# BLDC.net
KiCad netlist of a schematic drawn in EasyEDA Pro
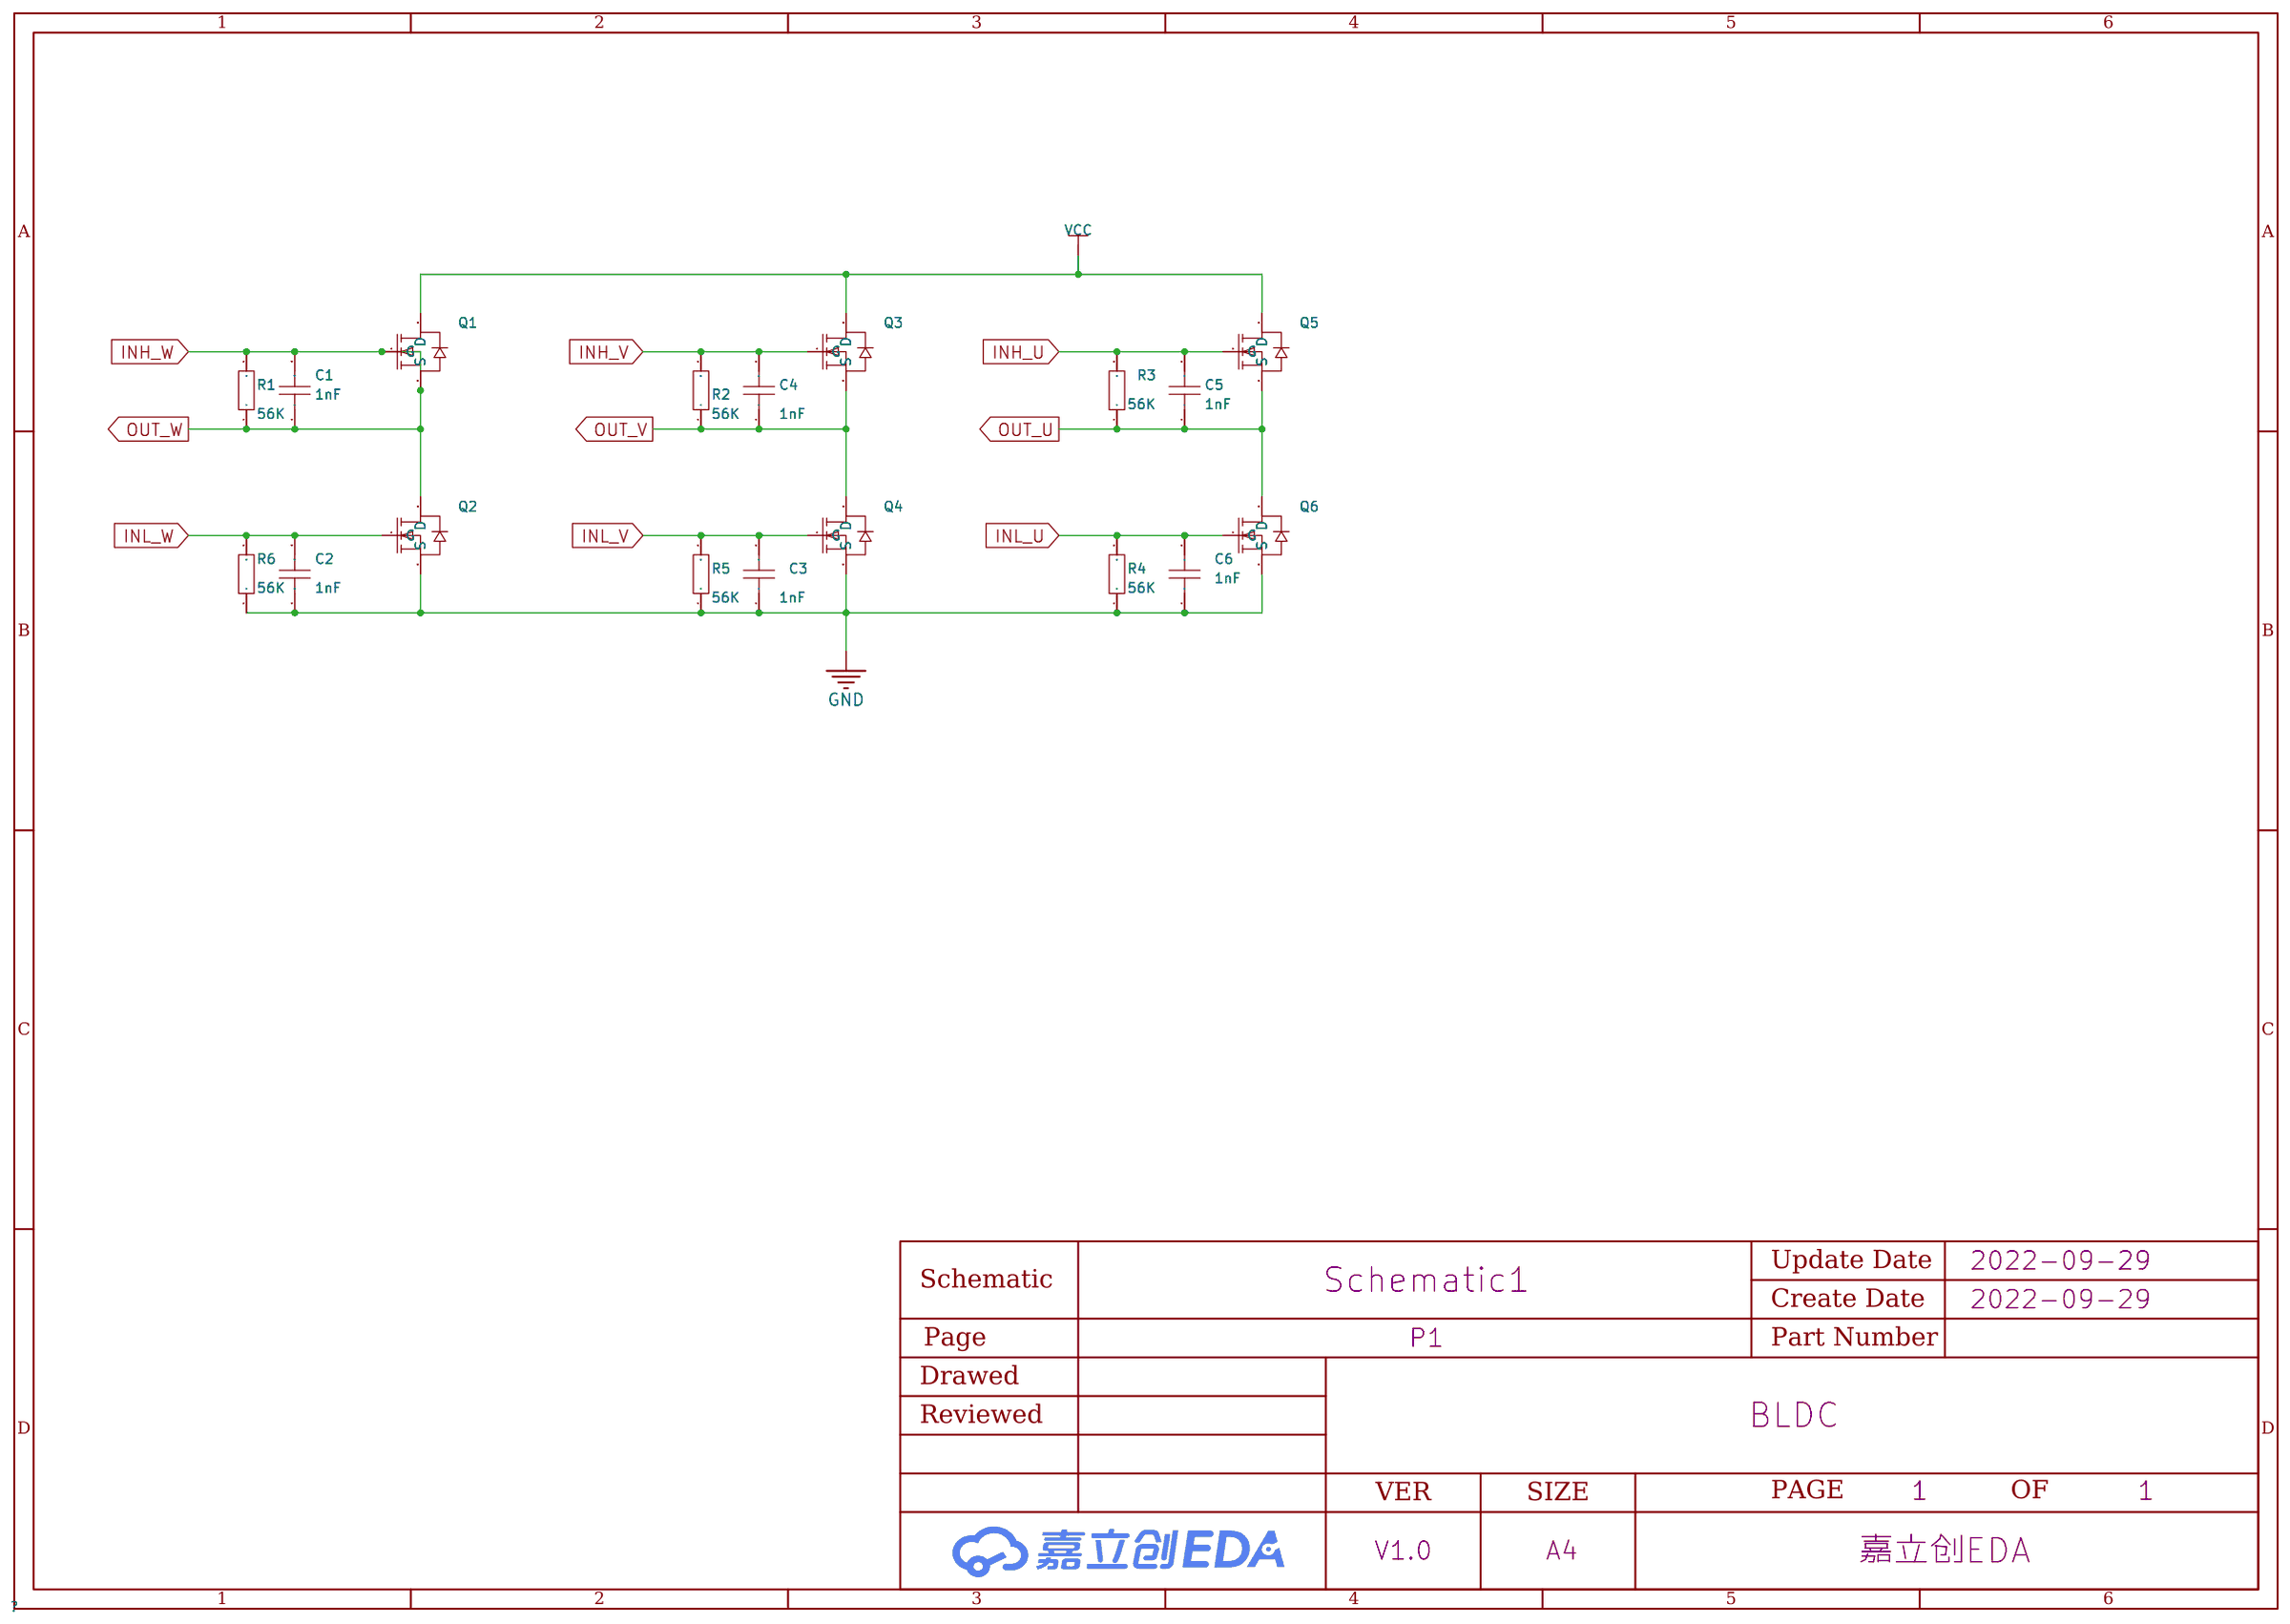
[diagram p0: schematic sheet]

(export (version "E")
  (design (tool "Eeschema 10.0.6"))
  (components
    (comp (ref "C1")
      (value "1nF")
      (footprint "easyedapro:C0603")
      (libsource (lib "easyedapro") (part "C1210X7R475K630NT"))
    )
    (comp (ref "C2")
      (value "1nF")
      (footprint "easyedapro:C0603")
      (libsource (lib "easyedapro") (part "C1210X7R475K630NT"))
    )
    (comp (ref "C3")
      (value "1nF")
      (footprint "easyedapro:C0603")
      (libsource (lib "easyedapro") (part "C1210X7R475K630NT"))
    )
    (comp (ref "C4")
      (value "1nF")
      (footprint "easyedapro:C0603")
      (libsource (lib "easyedapro") (part "C1210X7R475K630NT"))
    )
    (comp (ref "C5")
      (value "1nF")
      (footprint "easyedapro:C0603")
      (libsource (lib "easyedapro") (part "C1210X7R475K630NT"))
    )
    (comp (ref "C6")
      (value "1nF")
      (footprint "easyedapro:C0603")
      (libsource (lib "easyedapro") (part "C1210X7R475K630NT"))
    )
    (comp (ref "Q1")
      (value "~")
      (footprint "easyedapro:SOT-23-3_L2.9-W1.3-P1.90-LS2.4-BR")
      (libsource (lib "easyedapro") (part "N_MOS"))
    )
    (comp (ref "Q2")
      (value "~")
      (footprint "easyedapro:SOT-23-3_L2.9-W1.3-P1.90-LS2.4-BR")
      (libsource (lib "easyedapro") (part "N_MOS"))
    )
    (comp (ref "Q3")
      (value "~")
      (footprint "easyedapro:SOT-23-3_L2.9-W1.3-P1.90-LS2.4-BR")
      (libsource (lib "easyedapro") (part "N_MOS"))
    )
    (comp (ref "Q4")
      (value "~")
      (footprint "easyedapro:SOT-23-3_L2.9-W1.3-P1.90-LS2.4-BR")
      (libsource (lib "easyedapro") (part "N_MOS"))
    )
    (comp (ref "Q5")
      (value "~")
      (footprint "easyedapro:SOT-23-3_L2.9-W1.3-P1.90-LS2.4-BR")
      (libsource (lib "easyedapro") (part "N_MOS"))
    )
    (comp (ref "Q6")
      (value "~")
      (footprint "easyedapro:SOT-23-3_L2.9-W1.3-P1.90-LS2.4-BR")
      (libsource (lib "easyedapro") (part "N_MOS"))
    )
    (comp (ref "R1") (value "56K") (footprint "easyedapro:R0603") (libsource (lib "easyedapro") (part "电阻")))
    (comp (ref "R2") (value "56K") (footprint "easyedapro:R0603") (libsource (lib "easyedapro") (part "电阻")))
    (comp (ref "R3") (value "56K") (footprint "easyedapro:R0603") (libsource (lib "easyedapro") (part "电阻")))
    (comp (ref "R4") (value "56K") (footprint "easyedapro:R0603") (libsource (lib "easyedapro") (part "电阻")))
    (comp (ref "R5") (value "56K") (footprint "easyedapro:R0603") (libsource (lib "easyedapro") (part "电阻")))
    (comp (ref "R6") (value "56K") (footprint "easyedapro:R0603") (libsource (lib "easyedapro") (part "电阻")))
  )
  (nets
    (net (code "1") (name "GND") (class "Default")
      (node (ref "C2") (pin "1") (pinfunction "1_1") (pintype "input"))
      (node (ref "C3") (pin "1") (pinfunction "1_1") (pintype "input"))
      (node (ref "C6") (pin "1") (pinfunction "1_1") (pintype "input"))
      (node (ref "Q2") (pin "2") (pinfunction "S_2") (pintype "input"))
      (node (ref "Q4") (pin "2") (pinfunction "S_2") (pintype "input"))
      (node (ref "Q6") (pin "2") (pinfunction "S_2") (pintype "input"))
      (node (ref "R4") (pin "1") (pinfunction "1_1") (pintype "input"))
      (node (ref "R5") (pin "1") (pinfunction "1_1") (pintype "input"))
      (node (ref "R6") (pin "1") (pinfunction "1_1") (pintype "input"))
    )
    (net (code "2") (name "INH_U") (class "Default")
      (node (ref "C5") (pin "2") (pinfunction "2_2") (pintype "input"))
      (node (ref "Q5") (pin "1") (pinfunction "G_1") (pintype "input"))
      (node (ref "R3") (pin "2") (pinfunction "2_2") (pintype "input"))
    )
    (net (code "3") (name "INH_V") (class "Default")
      (node (ref "C4") (pin "2") (pinfunction "2_2") (pintype "input"))
      (node (ref "Q3") (pin "1") (pinfunction "G_1") (pintype "input"))
      (node (ref "R2") (pin "2") (pinfunction "2_2") (pintype "input"))
    )
    (net (code "4") (name "INH_W") (class "Default")
      (node (ref "C1") (pin "1") (pinfunction "1_1") (pintype "input"))
      (node (ref "C1") (pin "2") (pinfunction "2_2") (pintype "input"))
      (node (ref "Q1") (pin "1") (pinfunction "G_1") (pintype "input"))
      (node (ref "Q1") (pin "2") (pinfunction "S_2") (pintype "input"))
      (node (ref "Q2") (pin "3") (pinfunction "D_3") (pintype "input"))
      (node (ref "R1") (pin "1") (pinfunction "1_1") (pintype "input"))
      (node (ref "R1") (pin "2") (pinfunction "2_2") (pintype "input"))
    )
    (net (code "5") (name "INL_U") (class "Default")
      (node (ref "C6") (pin "2") (pinfunction "2_2") (pintype "input"))
      (node (ref "Q6") (pin "1") (pinfunction "G_1") (pintype "input"))
      (node (ref "R4") (pin "2") (pinfunction "2_2") (pintype "input"))
    )
    (net (code "6") (name "INL_V") (class "Default")
      (node (ref "C3") (pin "2") (pinfunction "2_2") (pintype "input"))
      (node (ref "Q4") (pin "1") (pinfunction "G_1") (pintype "input"))
      (node (ref "R5") (pin "2") (pinfunction "2_2") (pintype "input"))
    )
    (net (code "7") (name "INL_W") (class "Default")
      (node (ref "C2") (pin "2") (pinfunction "2_2") (pintype "input"))
      (node (ref "Q2") (pin "1") (pinfunction "G_1") (pintype "input"))
      (node (ref "R6") (pin "2") (pinfunction "2_2") (pintype "input"))
    )
    (net (code "8") (name "OUT_U") (class "Default")
      (node (ref "C5") (pin "1") (pinfunction "1_1") (pintype "input"))
      (node (ref "Q5") (pin "2") (pinfunction "S_2") (pintype "input"))
      (node (ref "Q6") (pin "3") (pinfunction "D_3") (pintype "input"))
      (node (ref "R3") (pin "1") (pinfunction "1_1") (pintype "input"))
    )
    (net (code "9") (name "OUT_V") (class "Default")
      (node (ref "C4") (pin "1") (pinfunction "1_1") (pintype "input"))
      (node (ref "Q3") (pin "2") (pinfunction "S_2") (pintype "input"))
      (node (ref "Q4") (pin "3") (pinfunction "D_3") (pintype "input"))
      (node (ref "R2") (pin "1") (pinfunction "1_1") (pintype "input"))
    )
    (net (code "10") (name "VCC") (class "Default")
      (node (ref "Q1") (pin "3") (pinfunction "D_3") (pintype "input"))
      (node (ref "Q3") (pin "3") (pinfunction "D_3") (pintype "input"))
      (node (ref "Q5") (pin "3") (pinfunction "D_3") (pintype "input"))
    )
  )
)
